# medusa-ai-audio.net
KiCad netlist of a schematic drawn in Altium Designer
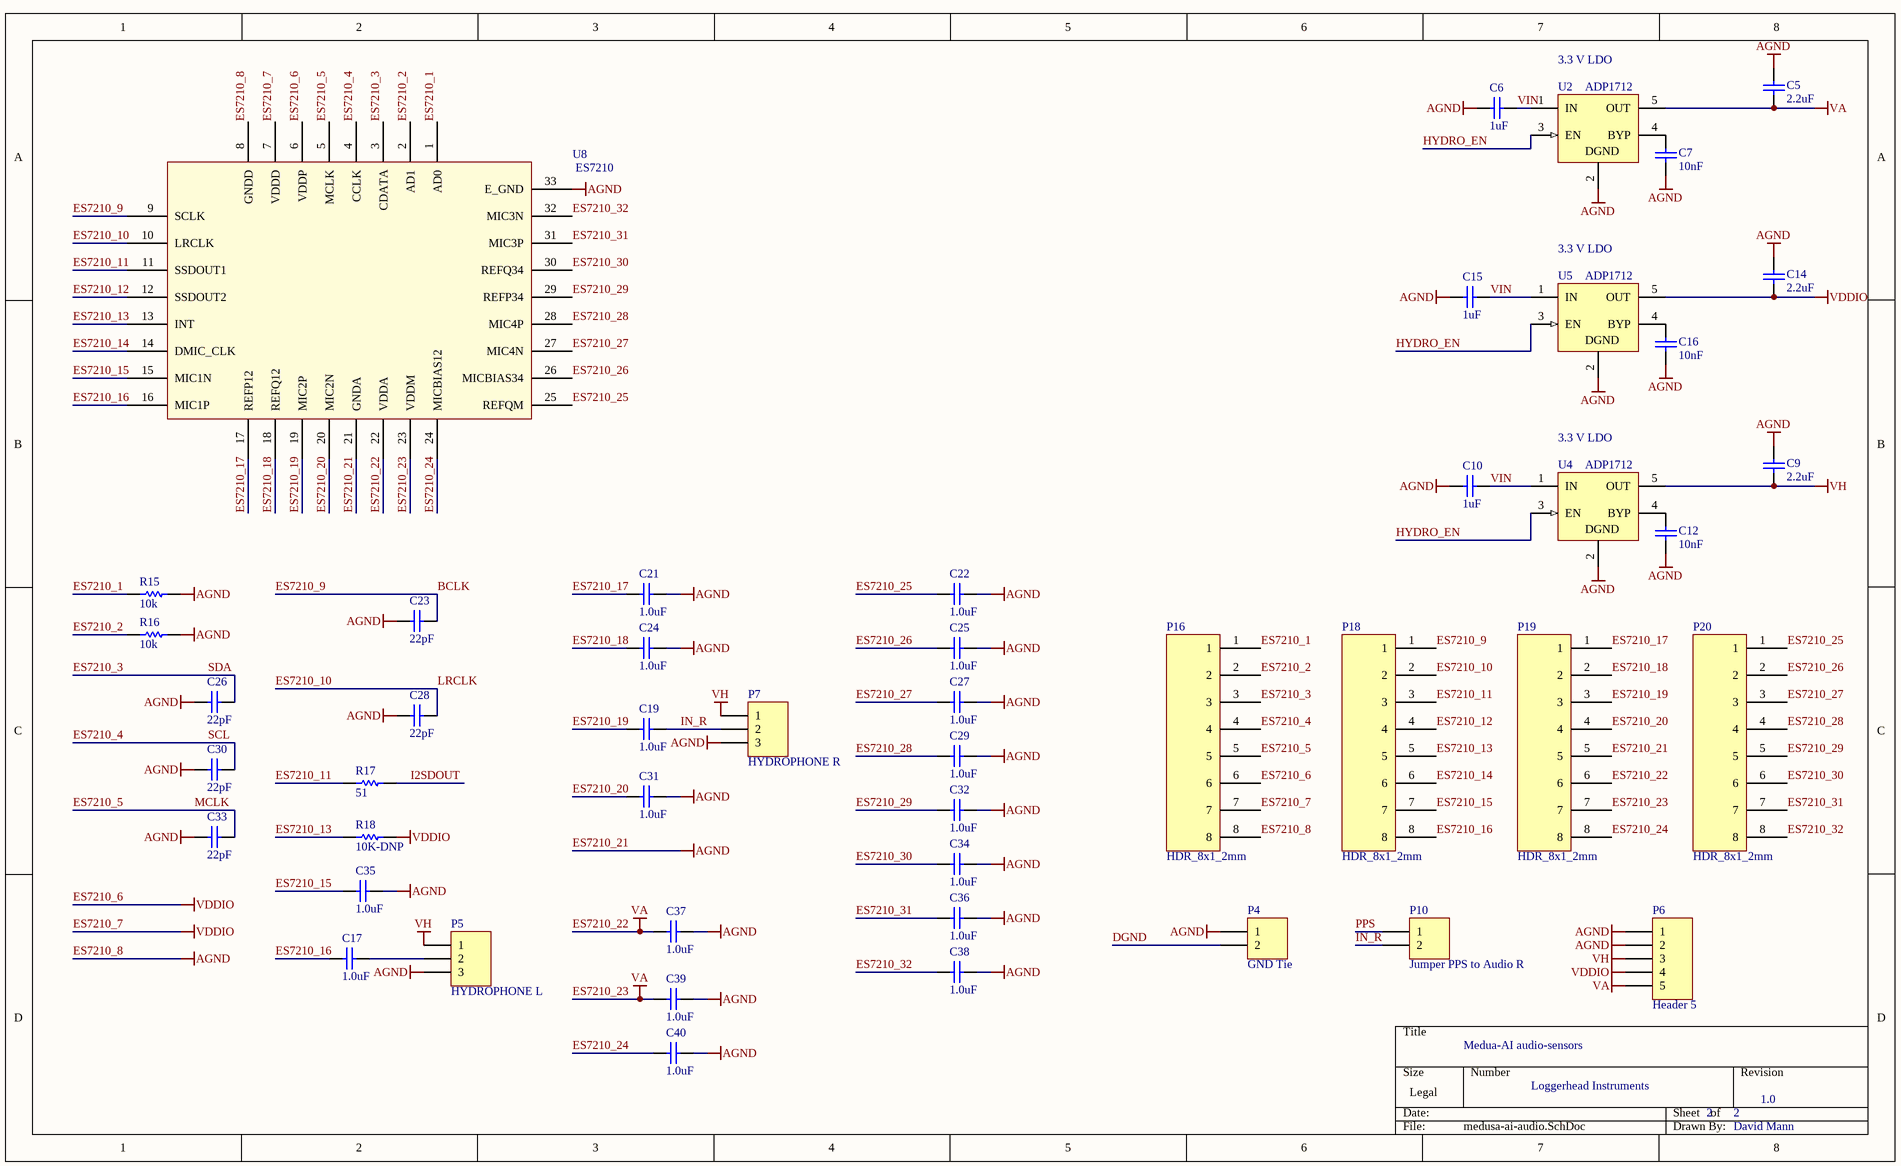
[diagram p0: medusa-ai-audio.SchDoc]

(export (version "E")
  (design (tool "Eeschema 10.0.6"))
  (components
    (comp (ref "C5")
      (value "2.2uF")
      (footprint "0402")
      (description "Ceramic Chip Capacitor - Standard")
      (fields (field (name "PUBLISHER") "Altium Limited"))
      (libsource (lib "KEMET Chip Capacitor") (part "C0402"))
    )
    (comp (ref "C6")
      (value "1uF")
      (footprint "0402")
      (description "Ceramic Chip Capacitor - Standard")
      (fields (field (name "PUBLISHER") "Altium Limited"))
      (libsource (lib "KEMET Chip Capacitor") (part "C0402"))
    )
    (comp (ref "C7")
      (value "10nF")
      (footprint "0402")
      (description "Ceramic Chip Capacitor - Standard")
      (fields (field (name "PUBLISHER") "Altium Limited"))
      (libsource (lib "KEMET Chip Capacitor") (part "C0402"))
    )
    (comp (ref "C9")
      (value "2.2uF")
      (footprint "0402")
      (description "Ceramic Chip Capacitor - Standard")
      (fields (field (name "PUBLISHER") "Altium Limited"))
      (libsource (lib "KEMET Chip Capacitor") (part "C0402"))
    )
    (comp (ref "C10")
      (value "1uF")
      (footprint "0402")
      (description "Ceramic Chip Capacitor - Standard")
      (fields (field (name "PUBLISHER") "Altium Limited"))
      (libsource (lib "KEMET Chip Capacitor") (part "C0402"))
    )
    (comp (ref "C12")
      (value "10nF")
      (footprint "0402")
      (description "Ceramic Chip Capacitor - Standard")
      (fields (field (name "PUBLISHER") "Altium Limited"))
      (libsource (lib "KEMET Chip Capacitor") (part "C0402"))
    )
    (comp (ref "C14")
      (value "2.2uF")
      (footprint "0402")
      (description "Ceramic Chip Capacitor - Standard")
      (fields (field (name "PUBLISHER") "Altium Limited"))
      (libsource (lib "KEMET Chip Capacitor") (part "C0402"))
    )
    (comp (ref "C15")
      (value "1uF")
      (footprint "0402")
      (description "Ceramic Chip Capacitor - Standard")
      (fields (field (name "PUBLISHER") "Altium Limited"))
      (libsource (lib "KEMET Chip Capacitor") (part "C0402"))
    )
    (comp (ref "C16")
      (value "10nF")
      (footprint "0402")
      (description "Ceramic Chip Capacitor - Standard")
      (fields (field (name "PUBLISHER") "Altium Limited"))
      (libsource (lib "KEMET Chip Capacitor") (part "C0402"))
    )
    (comp (ref "C17")
      (value "1.0uF")
      (footprint "0402")
      (description "Ceramic Chip Capacitor - Standard")
      (fields (field (name "PUBLISHER") "Altium Limited"))
      (libsource (lib "KEMET Chip Capacitor") (part "C0402"))
    )
    (comp (ref "C19")
      (value "1.0uF")
      (footprint "0402")
      (description "Ceramic Chip Capacitor - Standard")
      (fields (field (name "PUBLISHER") "Altium Limited"))
      (libsource (lib "KEMET Chip Capacitor") (part "C0402"))
    )
    (comp (ref "C21")
      (value "1.0uF")
      (footprint "0402")
      (description "Ceramic Chip Capacitor - Standard")
      (fields (field (name "PUBLISHER") "Altium Limited"))
      (libsource (lib "KEMET Chip Capacitor") (part "C0402"))
    )
    (comp (ref "C22")
      (value "1.0uF")
      (footprint "0402")
      (description "Ceramic Chip Capacitor - Standard")
      (fields (field (name "PUBLISHER") "Altium Limited"))
      (libsource (lib "KEMET Chip Capacitor") (part "C0402"))
    )
    (comp (ref "C23")
      (value "22pF")
      (footprint "0402")
      (description "Ceramic Chip Capacitor - Standard")
      (fields (field (name "PUBLISHER") "Altium Limited"))
      (libsource (lib "KEMET Chip Capacitor") (part "C0402"))
    )
    (comp (ref "C24")
      (value "1.0uF")
      (footprint "0402")
      (description "Ceramic Chip Capacitor - Standard")
      (fields (field (name "PUBLISHER") "Altium Limited"))
      (libsource (lib "KEMET Chip Capacitor") (part "C0402"))
    )
    (comp (ref "C25")
      (value "1.0uF")
      (footprint "0402")
      (description "Ceramic Chip Capacitor - Standard")
      (fields (field (name "PUBLISHER") "Altium Limited"))
      (libsource (lib "KEMET Chip Capacitor") (part "C0402"))
    )
    (comp (ref "C26")
      (value "22pF")
      (footprint "0402")
      (description "Ceramic Chip Capacitor - Standard")
      (fields (field (name "PUBLISHER") "Altium Limited"))
      (libsource (lib "KEMET Chip Capacitor") (part "C0402"))
    )
    (comp (ref "C27")
      (value "1.0uF")
      (footprint "0402")
      (description "Ceramic Chip Capacitor - Standard")
      (fields (field (name "PUBLISHER") "Altium Limited"))
      (libsource (lib "KEMET Chip Capacitor") (part "C0402"))
    )
    (comp (ref "C28")
      (value "22pF")
      (footprint "0402")
      (description "Ceramic Chip Capacitor - Standard")
      (fields (field (name "PUBLISHER") "Altium Limited"))
      (libsource (lib "KEMET Chip Capacitor") (part "C0402"))
    )
    (comp (ref "C29")
      (value "1.0uF")
      (footprint "0402")
      (description "Ceramic Chip Capacitor - Standard")
      (fields (field (name "PUBLISHER") "Altium Limited"))
      (libsource (lib "KEMET Chip Capacitor") (part "C0402"))
    )
    (comp (ref "C30")
      (value "22pF")
      (footprint "0402")
      (description "Ceramic Chip Capacitor - Standard")
      (fields (field (name "PUBLISHER") "Altium Limited"))
      (libsource (lib "KEMET Chip Capacitor") (part "C0402"))
    )
    (comp (ref "C31")
      (value "1.0uF")
      (footprint "0402")
      (description "Ceramic Chip Capacitor - Standard")
      (fields (field (name "PUBLISHER") "Altium Limited"))
      (libsource (lib "KEMET Chip Capacitor") (part "C0402"))
    )
    (comp (ref "C32")
      (value "1.0uF")
      (footprint "0402")
      (description "Ceramic Chip Capacitor - Standard")
      (fields (field (name "PUBLISHER") "Altium Limited"))
      (libsource (lib "KEMET Chip Capacitor") (part "C0402"))
    )
    (comp (ref "C33")
      (value "22pF")
      (footprint "0402")
      (description "Ceramic Chip Capacitor - Standard")
      (fields (field (name "PUBLISHER") "Altium Limited"))
      (libsource (lib "KEMET Chip Capacitor") (part "C0402"))
    )
    (comp (ref "C34")
      (value "1.0uF")
      (footprint "0402")
      (description "Ceramic Chip Capacitor - Standard")
      (fields (field (name "PUBLISHER") "Altium Limited"))
      (libsource (lib "KEMET Chip Capacitor") (part "C0402"))
    )
    (comp (ref "C35")
      (value "1.0uF")
      (footprint "0402")
      (description "Ceramic Chip Capacitor - Standard")
      (fields (field (name "PUBLISHER") "Altium Limited"))
      (libsource (lib "KEMET Chip Capacitor") (part "C0402"))
    )
    (comp (ref "C36")
      (value "1.0uF")
      (footprint "0402")
      (description "Ceramic Chip Capacitor - Standard")
      (fields (field (name "PUBLISHER") "Altium Limited"))
      (libsource (lib "KEMET Chip Capacitor") (part "C0402"))
    )
    (comp (ref "C37")
      (value "1.0uF")
      (footprint "0402")
      (description "Ceramic Chip Capacitor - Standard")
      (fields (field (name "PUBLISHER") "Altium Limited"))
      (libsource (lib "KEMET Chip Capacitor") (part "C0402"))
    )
    (comp (ref "C38")
      (value "1.0uF")
      (footprint "0402")
      (description "Ceramic Chip Capacitor - Standard")
      (fields (field (name "PUBLISHER") "Altium Limited"))
      (libsource (lib "KEMET Chip Capacitor") (part "C0402"))
    )
    (comp (ref "C39")
      (value "1.0uF")
      (footprint "0402")
      (description "Ceramic Chip Capacitor - Standard")
      (fields (field (name "PUBLISHER") "Altium Limited"))
      (libsource (lib "KEMET Chip Capacitor") (part "C0402"))
    )
    (comp (ref "C40")
      (value "1.0uF")
      (footprint "0402")
      (description "Ceramic Chip Capacitor - Standard")
      (fields (field (name "PUBLISHER") "Altium Limited"))
      (libsource (lib "KEMET Chip Capacitor") (part "C0402"))
    )
    (comp (ref "P4")
      (value "GND Tie")
      (footprint "HDR1X2")
      (description "Header, 2-Pin")
      (fields (field (name "PUBLISHER") "Altium Limited"))
      (libsource (lib "Miscellaneous Connectors") (part "Header 2"))
    )
    (comp (ref "P5")
      (value "HYDROPHONE L")
      (footprint "HDR1X3")
      (description "Header, 3-Pin")
      (fields (field (name "PUBLISHER") "Altium Limited"))
      (libsource (lib "Miscellaneous Connectors") (part "Header 3"))
    )
    (comp (ref "P6")
      (value "Header 5")
      (footprint "HDR1X5")
      (description "Header, 5-Pin")
      (fields (field (name "PUBLISHER") "Altium Limited"))
      (libsource (lib "Miscellaneous Connectors") (part "Header 5"))
    )
    (comp (ref "P7")
      (value "HYDROPHONE R")
      (footprint "HDR1X3")
      (description "Header, 3-Pin")
      (fields (field (name "PUBLISHER") "Altium Limited"))
      (libsource (lib "Miscellaneous Connectors") (part "Header 3"))
    )
    (comp (ref "P10")
      (value "Jumper PPS to Audio R")
      (footprint "HDR1X2")
      (description "Header, 2-Pin")
      (fields (field (name "PUBLISHER") "Altium Limited"))
      (libsource (lib "Miscellaneous Connectors") (part "Header 2"))
    )
    (comp (ref "P16")
      (value "HDR_8x1_2mm")
      (footprint "HDR_8x1_2mm")
      (libsource (lib "Loggerhead") (part "HDR_8x1_2mm"))
    )
    (comp (ref "P18")
      (value "HDR_8x1_2mm")
      (footprint "HDR_8x1_2mm")
      (libsource (lib "Loggerhead") (part "HDR_8x1_2mm"))
    )
    (comp (ref "P19")
      (value "HDR_8x1_2mm")
      (footprint "HDR_8x1_2mm")
      (libsource (lib "Loggerhead") (part "HDR_8x1_2mm"))
    )
    (comp (ref "P20")
      (value "HDR_8x1_2mm")
      (footprint "HDR_8x1_2mm")
      (libsource (lib "Loggerhead") (part "HDR_8x1_2mm"))
    )
    (comp (ref "R15")
      (value "10k")
      (footprint "3-0603")
      (fields (field (name "PUBLISHER") "Altium Limited"))
      (libsource (lib "Panasonic Resistor") (part "ERJ3RK"))
    )
    (comp (ref "R16")
      (value "10k")
      (footprint "3-0603")
      (fields (field (name "PUBLISHER") "Altium Limited"))
      (libsource (lib "Panasonic Resistor") (part "ERJ3RK"))
    )
    (comp (ref "R17")
      (value "51")
      (footprint "3-0603")
      (fields (field (name "PUBLISHER") "Altium Limited"))
      (libsource (lib "Panasonic Resistor") (part "ERJ3RK"))
    )
    (comp (ref "R18")
      (value "10K-DNP")
      (footprint "3-0603")
      (fields (field (name "PUBLISHER") "Altium Limited"))
      (libsource (lib "Panasonic Resistor") (part "ERJ3RK"))
    )
    (comp (ref "U2")
      (value "ADP1712")
      (footprint "MF05A_N")
      (description "Micropower, 150mA Low-Noise Ultra Low-Dropout CMOS Voltage Regulator")
      (fields
        (field (name "PARTNUMBER") "LP3985IM5-3.3")
        (field (name "MANUFACTURER") "National Semiconductor")
        (field (name "PUBLISHER") "Altium Limited")
      )
      (libsource (lib "NSC LDO") (part "LP3985IM5-3.3"))
    )
    (comp (ref "U4")
      (value "ADP1712")
      (footprint "MF05A_N")
      (description "Micropower, 150mA Low-Noise Ultra Low-Dropout CMOS Voltage Regulator")
      (fields
        (field (name "PARTNUMBER") "LP3985IM5-3.3")
        (field (name "MANUFACTURER") "National Semiconductor")
        (field (name "PUBLISHER") "Altium Limited")
      )
      (libsource (lib "NSC LDO") (part "LP3985IM5-3.3"))
    )
    (comp (ref "U5")
      (value "ADP1712")
      (footprint "MF05A_N")
      (description "Micropower, 150mA Low-Noise Ultra Low-Dropout CMOS Voltage Regulator")
      (fields
        (field (name "PARTNUMBER") "LP3985IM5-3.3")
        (field (name "MANUFACTURER") "National Semiconductor")
        (field (name "PUBLISHER") "Altium Limited")
      )
      (libsource (lib "NSC LDO") (part "LP3985IM5-3.3"))
    )
    (comp (ref "U8")
      (value "ES7210")
      (footprint "ES7210")
      (description "Audio CODEC")
      (libsource (lib "Loggerhead") (part "ES7210"))
    )
  )
  (nets
    (net (code "1") (name "/BCLK") (class "Default")
      (node (ref "C23") (pin "2") (pinfunction "2_2") (pintype "passive"))
      (node (ref "P18") (pin "1") (pinfunction "1_1") (pintype "passive"))
      (node (ref "U8") (pin "9") (pinfunction "SCLK_9") (pintype "passive"))
    )
    (net (code "2") (name "/DGND") (class "Default")
      (node (ref "P4") (pin "2") (pinfunction "2_2") (pintype "passive"))
    )
    (net (code "3") (name "/ES7210_1") (class "Default")
      (node (ref "P16") (pin "1") (pinfunction "1_1") (pintype "passive"))
      (node (ref "R15") (pin "1") (pinfunction "1_1") (pintype "passive"))
      (node (ref "U8") (pin "1") (pinfunction "AD0_1") (pintype "passive"))
    )
    (net (code "4") (name "/ES7210_2") (class "Default")
      (node (ref "P16") (pin "2") (pinfunction "2_2") (pintype "passive"))
      (node (ref "R16") (pin "1") (pinfunction "1_1") (pintype "passive"))
      (node (ref "U8") (pin "2") (pinfunction "AD1_2") (pintype "passive"))
    )
    (net (code "5") (name "/ES7210_3") (class "Default")
      (node (ref "C26") (pin "2") (pinfunction "2_2") (pintype "passive"))
      (node (ref "P16") (pin "3") (pinfunction "3_3") (pintype "passive"))
      (node (ref "U8") (pin "3") (pinfunction "CDATA_3") (pintype "passive"))
    )
    (net (code "6") (name "/ES7210_4") (class "Default")
      (node (ref "C30") (pin "2") (pinfunction "2_2") (pintype "passive"))
      (node (ref "P16") (pin "4") (pinfunction "4_4") (pintype "passive"))
      (node (ref "U8") (pin "4") (pinfunction "CCLK_4") (pintype "passive"))
    )
    (net (code "7") (name "/ES7210_5") (class "Default")
      (node (ref "C33") (pin "2") (pinfunction "2_2") (pintype "passive"))
      (node (ref "P16") (pin "5") (pinfunction "5_5") (pintype "passive"))
      (node (ref "U8") (pin "5") (pinfunction "MCLK_5") (pintype "passive"))
    )
    (net (code "8") (name "/ES7210_10") (class "Default")
      (node (ref "C28") (pin "2") (pinfunction "2_2") (pintype "passive"))
      (node (ref "P18") (pin "2") (pinfunction "2_2") (pintype "passive"))
      (node (ref "U8") (pin "10") (pinfunction "LRCLK_10") (pintype "passive"))
    )
    (net (code "9") (name "/ES7210_11") (class "Default")
      (node (ref "P18") (pin "3") (pinfunction "3_3") (pintype "passive"))
      (node (ref "R17") (pin "1") (pinfunction "1_1") (pintype "passive"))
      (node (ref "U8") (pin "11") (pinfunction "SSDOUT1_11") (pintype "passive"))
    )
    (net (code "10") (name "/ES7210_12") (class "Default")
      (node (ref "P18") (pin "4") (pinfunction "4_4") (pintype "passive"))
      (node (ref "U8") (pin "12") (pinfunction "SSDOUT2_12") (pintype "passive"))
    )
    (net (code "11") (name "/ES7210_13") (class "Default")
      (node (ref "P18") (pin "5") (pinfunction "5_5") (pintype "passive"))
      (node (ref "R18") (pin "1") (pinfunction "1_1") (pintype "passive"))
      (node (ref "U8") (pin "13") (pinfunction "INT_13") (pintype "passive"))
    )
    (net (code "12") (name "/ES7210_14") (class "Default")
      (node (ref "P18") (pin "6") (pinfunction "6_6") (pintype "passive"))
      (node (ref "U8") (pin "14") (pinfunction "DMIC_CLK_14") (pintype "passive"))
    )
    (net (code "13") (name "/ES7210_15") (class "Default")
      (node (ref "C35") (pin "2") (pinfunction "2_2") (pintype "passive"))
      (node (ref "P18") (pin "7") (pinfunction "7_7") (pintype "passive"))
      (node (ref "U8") (pin "15") (pinfunction "MIC1N_15") (pintype "passive"))
    )
    (net (code "14") (name "/ES7210_16") (class "Default")
      (node (ref "C17") (pin "2") (pinfunction "2_2") (pintype "passive"))
      (node (ref "P18") (pin "8") (pinfunction "8_8") (pintype "passive"))
      (node (ref "U8") (pin "16") (pinfunction "MIC1P_16") (pintype "passive"))
    )
    (net (code "15") (name "/ES7210_17") (class "Default")
      (node (ref "C21") (pin "2") (pinfunction "2_2") (pintype "passive"))
      (node (ref "P19") (pin "1") (pinfunction "1_1") (pintype "passive"))
      (node (ref "U8") (pin "17") (pinfunction "REFP12_17") (pintype "passive"))
    )
    (net (code "16") (name "/ES7210_18") (class "Default")
      (node (ref "C24") (pin "2") (pinfunction "2_2") (pintype "passive"))
      (node (ref "P19") (pin "2") (pinfunction "2_2") (pintype "passive"))
      (node (ref "U8") (pin "18") (pinfunction "REFQ12_18") (pintype "passive"))
    )
    (net (code "17") (name "/ES7210_19") (class "Default")
      (node (ref "C19") (pin "2") (pinfunction "2_2") (pintype "passive"))
      (node (ref "P19") (pin "3") (pinfunction "3_3") (pintype "passive"))
      (node (ref "U8") (pin "19") (pinfunction "MIC2P_19") (pintype "passive"))
    )
    (net (code "18") (name "/ES7210_20") (class "Default")
      (node (ref "C31") (pin "2") (pinfunction "2_2") (pintype "passive"))
      (node (ref "P19") (pin "4") (pinfunction "4_4") (pintype "passive"))
      (node (ref "U8") (pin "20") (pinfunction "MIC2N_20") (pintype "passive"))
    )
    (net (code "19") (name "/ES7210_24") (class "Default")
      (node (ref "C40") (pin "2") (pinfunction "2_2") (pintype "passive"))
      (node (ref "P19") (pin "8") (pinfunction "8_8") (pintype "passive"))
      (node (ref "U8") (pin "24") (pinfunction "MICBIAS12_24") (pintype "passive"))
    )
    (net (code "20") (name "/ES7210_25") (class "Default")
      (node (ref "C22") (pin "2") (pinfunction "2_2") (pintype "passive"))
      (node (ref "P20") (pin "1") (pinfunction "1_1") (pintype "passive"))
      (node (ref "U8") (pin "25") (pinfunction "REFQM_25") (pintype "passive"))
    )
    (net (code "21") (name "/ES7210_26") (class "Default")
      (node (ref "C25") (pin "2") (pinfunction "2_2") (pintype "passive"))
      (node (ref "P20") (pin "2") (pinfunction "2_2") (pintype "passive"))
      (node (ref "U8") (pin "26") (pinfunction "MICBIAS34_26") (pintype "passive"))
    )
    (net (code "22") (name "/ES7210_27") (class "Default")
      (node (ref "C27") (pin "2") (pinfunction "2_2") (pintype "passive"))
      (node (ref "P20") (pin "3") (pinfunction "3_3") (pintype "passive"))
      (node (ref "U8") (pin "27") (pinfunction "MIC4N_27") (pintype "passive"))
    )
    (net (code "23") (name "/ES7210_28") (class "Default")
      (node (ref "C29") (pin "2") (pinfunction "2_2") (pintype "passive"))
      (node (ref "P20") (pin "4") (pinfunction "4_4") (pintype "passive"))
      (node (ref "U8") (pin "28") (pinfunction "MIC4P_28") (pintype "passive"))
    )
    (net (code "24") (name "/ES7210_29") (class "Default")
      (node (ref "C32") (pin "2") (pinfunction "2_2") (pintype "passive"))
      (node (ref "P20") (pin "5") (pinfunction "5_5") (pintype "passive"))
      (node (ref "U8") (pin "29") (pinfunction "REFP34_29") (pintype "passive"))
    )
    (net (code "25") (name "/ES7210_30") (class "Default")
      (node (ref "C34") (pin "2") (pinfunction "2_2") (pintype "passive"))
      (node (ref "P20") (pin "6") (pinfunction "6_6") (pintype "passive"))
      (node (ref "U8") (pin "30") (pinfunction "REFQ34_30") (pintype "passive"))
    )
    (net (code "26") (name "/ES7210_31") (class "Default")
      (node (ref "C36") (pin "2") (pinfunction "2_2") (pintype "passive"))
      (node (ref "P20") (pin "7") (pinfunction "7_7") (pintype "passive"))
      (node (ref "U8") (pin "31") (pinfunction "MIC3P_31") (pintype "passive"))
    )
    (net (code "27") (name "/ES7210_32") (class "Default")
      (node (ref "C38") (pin "2") (pinfunction "2_2") (pintype "passive"))
      (node (ref "P20") (pin "8") (pinfunction "8_8") (pintype "passive"))
      (node (ref "U8") (pin "32") (pinfunction "MIC3N_32") (pintype "passive"))
    )
    (net (code "28") (name "/HYDRO_EN") (class "Default")
      (node (ref "U2") (pin "3") (pinfunction "EN_3") (pintype "input"))
      (node (ref "U4") (pin "3") (pinfunction "EN_3") (pintype "input"))
      (node (ref "U5") (pin "3") (pinfunction "EN_3") (pintype "input"))
    )
    (net (code "29") (name "/I2SDOUT") (class "Default")
      (node (ref "R17") (pin "2") (pinfunction "2_2") (pintype "passive"))
    )
    (net (code "30") (name "/IN_R") (class "Default")
      (node (ref "C19") (pin "1") (pinfunction "1_1") (pintype "passive"))
      (node (ref "P10") (pin "2") (pinfunction "2_2") (pintype "passive"))
      (node (ref "P7") (pin "2") (pinfunction "2_2") (pintype "passive"))
    )
    (net (code "31") (name "/PPS") (class "Default")
      (node (ref "P10") (pin "1") (pinfunction "1_1") (pintype "passive"))
    )
    (net (code "32") (name "/VIN") (class "Default")
      (node (ref "C10") (pin "1") (pinfunction "1_1") (pintype "passive"))
      (node (ref "C15") (pin "1") (pinfunction "1_1") (pintype "passive"))
      (node (ref "C6") (pin "1") (pinfunction "1_1") (pintype "passive"))
      (node (ref "U2") (pin "1") (pinfunction "IN_1") (pintype "power_in"))
      (node (ref "U4") (pin "1") (pinfunction "IN_1") (pintype "power_in"))
      (node (ref "U5") (pin "1") (pinfunction "IN_1") (pintype "power_in"))
    )
    (net (code "33") (name "AGND") (class "Default")
      (node (ref "C10") (pin "2") (pinfunction "2_2") (pintype "passive"))
      (node (ref "C12") (pin "2") (pinfunction "2_2") (pintype "passive"))
      (node (ref "C14") (pin "2") (pinfunction "2_2") (pintype "passive"))
      (node (ref "C15") (pin "2") (pinfunction "2_2") (pintype "passive"))
      (node (ref "C16") (pin "2") (pinfunction "2_2") (pintype "passive"))
      (node (ref "C21") (pin "1") (pinfunction "1_1") (pintype "passive"))
      (node (ref "C22") (pin "1") (pinfunction "1_1") (pintype "passive"))
      (node (ref "C23") (pin "1") (pinfunction "1_1") (pintype "passive"))
      (node (ref "C24") (pin "1") (pinfunction "1_1") (pintype "passive"))
      (node (ref "C25") (pin "1") (pinfunction "1_1") (pintype "passive"))
      (node (ref "C26") (pin "1") (pinfunction "1_1") (pintype "passive"))
      (node (ref "C27") (pin "1") (pinfunction "1_1") (pintype "passive"))
      (node (ref "C28") (pin "1") (pinfunction "1_1") (pintype "passive"))
      (node (ref "C29") (pin "1") (pinfunction "1_1") (pintype "passive"))
      (node (ref "C30") (pin "1") (pinfunction "1_1") (pintype "passive"))
      (node (ref "C31") (pin "1") (pinfunction "1_1") (pintype "passive"))
      (node (ref "C32") (pin "1") (pinfunction "1_1") (pintype "passive"))
      (node (ref "C33") (pin "1") (pinfunction "1_1") (pintype "passive"))
      (node (ref "C34") (pin "1") (pinfunction "1_1") (pintype "passive"))
      (node (ref "C35") (pin "1") (pinfunction "1_1") (pintype "passive"))
      (node (ref "C36") (pin "1") (pinfunction "1_1") (pintype "passive"))
      (node (ref "C37") (pin "1") (pinfunction "1_1") (pintype "passive"))
      (node (ref "C38") (pin "1") (pinfunction "1_1") (pintype "passive"))
      (node (ref "C39") (pin "1") (pinfunction "1_1") (pintype "passive"))
      (node (ref "C40") (pin "1") (pinfunction "1_1") (pintype "passive"))
      (node (ref "C5") (pin "2") (pinfunction "2_2") (pintype "passive"))
      (node (ref "C6") (pin "2") (pinfunction "2_2") (pintype "passive"))
      (node (ref "C7") (pin "2") (pinfunction "2_2") (pintype "passive"))
      (node (ref "C9") (pin "2") (pinfunction "2_2") (pintype "passive"))
      (node (ref "P16") (pin "8") (pinfunction "8_8") (pintype "passive"))
      (node (ref "P19") (pin "5") (pinfunction "5_5") (pintype "passive"))
      (node (ref "P4") (pin "1") (pinfunction "1_1") (pintype "passive"))
      (node (ref "P5") (pin "3") (pinfunction "3_3") (pintype "passive"))
      (node (ref "P6") (pin "1") (pinfunction "1_1") (pintype "passive"))
      (node (ref "P6") (pin "2") (pinfunction "2_2") (pintype "passive"))
      (node (ref "P7") (pin "3") (pinfunction "3_3") (pintype "passive"))
      (node (ref "R15") (pin "2") (pinfunction "2_2") (pintype "passive"))
      (node (ref "R16") (pin "2") (pinfunction "2_2") (pintype "passive"))
      (node (ref "U2") (pin "2") (pinfunction "GND_2") (pintype "power_in"))
      (node (ref "U4") (pin "2") (pinfunction "GND_2") (pintype "power_in"))
      (node (ref "U5") (pin "2") (pinfunction "GND_2") (pintype "power_in"))
      (node (ref "U8") (pin "21") (pinfunction "GNDA_21") (pintype "passive"))
      (node (ref "U8") (pin "33") (pinfunction "E_GND_33") (pintype "passive"))
      (node (ref "U8") (pin "8") (pinfunction "GNDD_8") (pintype "passive"))
    )
    (net (code "34") (name "Net-(C17-Pad1)") (class "Default")
      (node (ref "C17") (pin "1") (pinfunction "1_1") (pintype "passive"))
      (node (ref "P5") (pin "2") (pinfunction "2_2") (pintype "passive"))
    )
    (net (code "35") (name "Net-(U2-BYP)") (class "Default")
      (node (ref "C7") (pin "1") (pinfunction "1_1") (pintype "passive"))
      (node (ref "U2") (pin "4") (pinfunction "BYP_4") (pintype "passive"))
    )
    (net (code "36") (name "Net-(U4-BYP)") (class "Default")
      (node (ref "C12") (pin "1") (pinfunction "1_1") (pintype "passive"))
      (node (ref "U4") (pin "4") (pinfunction "BYP_4") (pintype "passive"))
    )
    (net (code "37") (name "Net-(U5-BYP)") (class "Default")
      (node (ref "C16") (pin "1") (pinfunction "1_1") (pintype "passive"))
      (node (ref "U5") (pin "4") (pinfunction "BYP_4") (pintype "passive"))
    )
    (net (code "38") (name "VA") (class "Default")
      (node (ref "C37") (pin "2") (pinfunction "2_2") (pintype "passive"))
      (node (ref "C39") (pin "2") (pinfunction "2_2") (pintype "passive"))
      (node (ref "C5") (pin "1") (pinfunction "1_1") (pintype "passive"))
      (node (ref "P19") (pin "6") (pinfunction "6_6") (pintype "passive"))
      (node (ref "P19") (pin "7") (pinfunction "7_7") (pintype "passive"))
      (node (ref "P6") (pin "5") (pinfunction "5_5") (pintype "passive"))
      (node (ref "U2") (pin "5") (pinfunction "OUT_5") (pintype "power_in"))
      (node (ref "U8") (pin "22") (pinfunction "VDDA_22") (pintype "passive"))
      (node (ref "U8") (pin "23") (pinfunction "VDDM_23") (pintype "passive"))
    )
    (net (code "39") (name "VDDIO") (class "Default")
      (node (ref "C14") (pin "1") (pinfunction "1_1") (pintype "passive"))
      (node (ref "P16") (pin "6") (pinfunction "6_6") (pintype "passive"))
      (node (ref "P16") (pin "7") (pinfunction "7_7") (pintype "passive"))
      (node (ref "P6") (pin "4") (pinfunction "4_4") (pintype "passive"))
      (node (ref "R18") (pin "2") (pinfunction "2_2") (pintype "passive"))
      (node (ref "U5") (pin "5") (pinfunction "OUT_5") (pintype "power_in"))
      (node (ref "U8") (pin "6") (pinfunction "VDDP_6") (pintype "passive"))
      (node (ref "U8") (pin "7") (pinfunction "VDDD_7") (pintype "passive"))
    )
    (net (code "40") (name "VH") (class "Default")
      (node (ref "C9") (pin "1") (pinfunction "1_1") (pintype "passive"))
      (node (ref "P5") (pin "1") (pinfunction "1_1") (pintype "passive"))
      (node (ref "P6") (pin "3") (pinfunction "3_3") (pintype "passive"))
      (node (ref "P7") (pin "1") (pinfunction "1_1") (pintype "passive"))
      (node (ref "U4") (pin "5") (pinfunction "OUT_5") (pintype "power_in"))
    )
  )
)
